# Nixie_Power_Suppy_v2_0_1.net
KiCad netlist of a schematic drawn in EAGLE
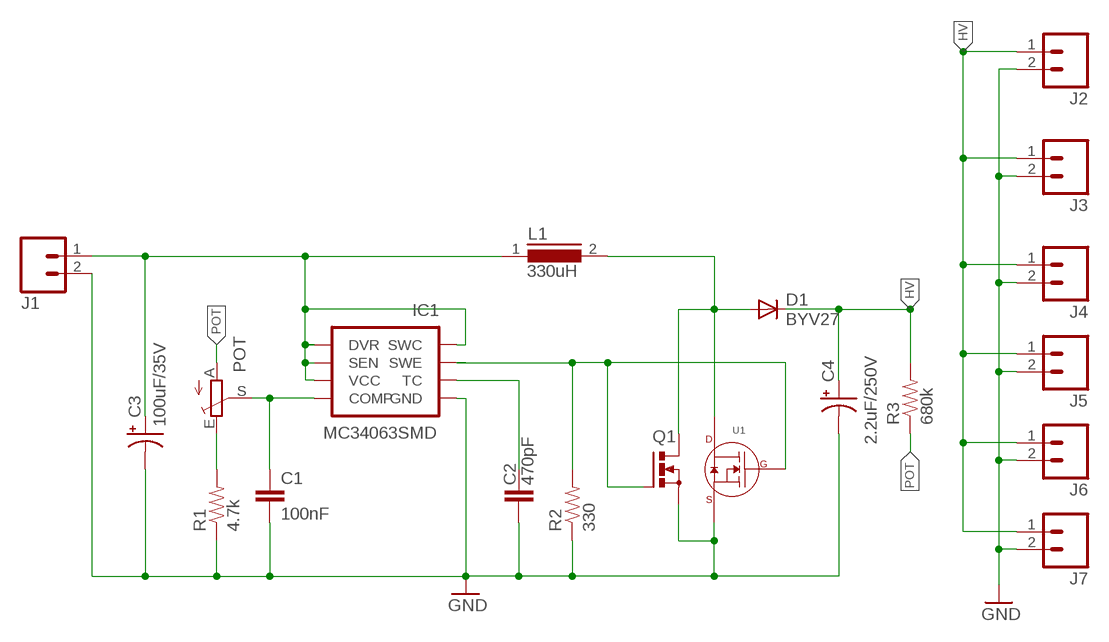
[diagram p0: schematic, sheet 1]

(export (version "E")
  (design (tool "Eeschema 10.0.6"))
  (components
    (comp (ref "C1")
      (value "100nF")
      (footprint "eagle-import:0805")
      (libsource (lib "eagle-import") (part "CAP0805"))
    )
    (comp (ref "C2")
      (value "470pF")
      (footprint "eagle-import:0805")
      (libsource (lib "eagle-import") (part "CAP0805"))
    )
    (comp (ref "C3")
      (value "100uF/35V")
      (footprint "eagle-import:CPOL-RADIAL-100UF-25V")
      (libsource (lib "eagle-import") (part "CAP_POLPTH1"))
    )
    (comp (ref "C4")
      (value "2.2uF/250V")
      (footprint "eagle-import:CPOL-RADIAL-100UF-25V")
      (libsource (lib "eagle-import") (part "CAP_POLPTH1"))
    )
    (comp (ref "D1")
      (value "BYV27")
      (footprint "eagle-import:SOD57-10")
      (libsource (lib "eagle-import") (part "BYV27"))
    )
    (comp (ref "IC1")
      (value "MC34063SMD")
      (footprint "eagle-import:SO08")
      (libsource (lib "eagle-import") (part "MC34063SMD"))
    )
    (comp (ref "J1")
      (value "M02LOCK")
      (footprint "eagle-import:1X02_LOCK")
      (libsource (lib "eagle-import") (part "M02LOCK"))
    )
    (comp (ref "J2")
      (value "M02LOCK")
      (footprint "eagle-import:1X02_LOCK")
      (libsource (lib "eagle-import") (part "M02LOCK"))
    )
    (comp (ref "J3")
      (value "M02LOCK")
      (footprint "eagle-import:1X02_LOCK")
      (libsource (lib "eagle-import") (part "M02LOCK"))
    )
    (comp (ref "J4")
      (value "M02LOCK")
      (footprint "eagle-import:1X02_LOCK")
      (libsource (lib "eagle-import") (part "M02LOCK"))
    )
    (comp (ref "J5")
      (value "M02LOCK")
      (footprint "eagle-import:1X02_LOCK")
      (libsource (lib "eagle-import") (part "M02LOCK"))
    )
    (comp (ref "J6")
      (value "M02LOCK")
      (footprint "eagle-import:1X02_LOCK")
      (libsource (lib "eagle-import") (part "M02LOCK"))
    )
    (comp (ref "J7")
      (value "M02LOCK")
      (footprint "eagle-import:1X02_LOCK")
      (libsource (lib "eagle-import") (part "M02LOCK"))
    )
    (comp (ref "L1")
      (value "330uH")
      (footprint "eagle-import:DR74")
      (libsource (lib "eagle-import") (part "DR74"))
    )
    (comp (ref "POT")
      (value "TRIM_EU-CA6V")
      (footprint "eagle-import:CA6V")
      (libsource (lib "eagle-import") (part "TRIM_EU-CA6V"))
    )
    (comp (ref "Q1")
      (value "PMOSFET_NTO220BV")
      (footprint "eagle-import:TO220BV")
      (libsource (lib "eagle-import") (part "PMOSFET_NTO220BV"))
    )
    (comp (ref "R1")
      (value "4.7k")
      (footprint "eagle-import:0805")
      (libsource (lib "eagle-import") (part "RESISTOR0805-RES"))
    )
    (comp (ref "R2")
      (value "330")
      (footprint "eagle-import:0805")
      (libsource (lib "eagle-import") (part "RESISTOR0805-RES"))
    )
    (comp (ref "R3")
      (value "680k")
      (footprint "eagle-import:0805")
      (libsource (lib "eagle-import") (part "RESISTOR0805-RES"))
    )
    (comp (ref "U1")
      (value "MOSFET_N-CHANNEL_SINGLE_TO-252-3")
      (footprint "eagle-import:TO-252-3")
      (libsource (lib "eagle-import") (part "MOSFET_N-CHANNEL_SINGLE_TO-252-3"))
    )
  )
  (nets
    (net (code "1") (name "GND") (class "Default")
      (node (ref "C1") (pin "2") (pinfunction "2_2") (pintype "passive"))
      (node (ref "C2") (pin "2") (pinfunction "2_2") (pintype "passive"))
      (node (ref "C3") (pin "2") (pinfunction "-_2") (pintype "passive"))
      (node (ref "C4") (pin "2") (pinfunction "-_2") (pintype "passive"))
      (node (ref "IC1") (pin "4") (pinfunction "GND_4") (pintype "bidirectional"))
      (node (ref "J1") (pin "2") (pinfunction "2_2") (pintype "passive"))
      (node (ref "J2") (pin "2") (pinfunction "2_2") (pintype "passive"))
      (node (ref "J3") (pin "2") (pinfunction "2_2") (pintype "passive"))
      (node (ref "J4") (pin "2") (pinfunction "2_2") (pintype "passive"))
      (node (ref "J5") (pin "2") (pinfunction "2_2") (pintype "passive"))
      (node (ref "J6") (pin "2") (pinfunction "2_2") (pintype "passive"))
      (node (ref "J7") (pin "2") (pinfunction "2_2") (pintype "passive"))
      (node (ref "Q1") (pin "S") (pinfunction "S_S") (pintype "passive"))
      (node (ref "R1") (pin "1") (pinfunction "1_1") (pintype "passive"))
      (node (ref "R2") (pin "1") (pinfunction "1_1") (pintype "passive"))
      (node (ref "U1") (pin "3") (pinfunction "SOURCE_3") (pintype "bidirectional"))
    )
    (net (code "2") (name "HV") (class "Default")
      (node (ref "C4") (pin "1") (pinfunction "+_1") (pintype "passive"))
      (node (ref "D1") (pin "C") (pinfunction "C_C") (pintype "passive"))
      (node (ref "J2") (pin "1") (pinfunction "1_1") (pintype "passive"))
      (node (ref "J3") (pin "1") (pinfunction "1_1") (pintype "passive"))
      (node (ref "J4") (pin "1") (pinfunction "1_1") (pintype "passive"))
      (node (ref "J5") (pin "1") (pinfunction "1_1") (pintype "passive"))
      (node (ref "J6") (pin "1") (pinfunction "1_1") (pintype "passive"))
      (node (ref "J7") (pin "1") (pinfunction "1_1") (pintype "passive"))
      (node (ref "R3") (pin "2") (pinfunction "2_2") (pintype "passive"))
    )
    (net (code "3") (name "Net-(C3-+)") (class "Default")
      (node (ref "C3") (pin "1") (pinfunction "+_1") (pintype "passive"))
      (node (ref "IC1") (pin "1") (pinfunction "SWC_1") (pintype "bidirectional"))
      (node (ref "IC1") (pin "6") (pinfunction "VCC_6") (pintype "bidirectional"))
      (node (ref "IC1") (pin "7") (pinfunction "SEN_7") (pintype "bidirectional"))
      (node (ref "IC1") (pin "8") (pinfunction "DVR_8") (pintype "bidirectional"))
      (node (ref "J1") (pin "1") (pinfunction "1_1") (pintype "passive"))
      (node (ref "L1") (pin "1") (pinfunction "1_1") (pintype "passive"))
    )
    (net (code "4") (name "Net-(IC1-COMP)") (class "Default")
      (node (ref "C1") (pin "1") (pinfunction "1_1") (pintype "passive"))
      (node (ref "IC1") (pin "5") (pinfunction "COMP_5") (pintype "bidirectional"))
      (node (ref "POT") (pin "S") (pinfunction "S_S") (pintype "passive"))
    )
    (net (code "5") (name "Net-(IC1-SWE)") (class "Default")
      (node (ref "IC1") (pin "2") (pinfunction "SWE_2") (pintype "bidirectional"))
      (node (ref "Q1") (pin "G") (pinfunction "G_G") (pintype "passive"))
      (node (ref "R2") (pin "2") (pinfunction "2_2") (pintype "passive"))
      (node (ref "U1") (pin "1") (pinfunction "GATE_1") (pintype "bidirectional"))
    )
    (net (code "6") (name "Net-(IC1-TC)") (class "Default")
      (node (ref "C2") (pin "1") (pinfunction "1_1") (pintype "passive"))
      (node (ref "IC1") (pin "3") (pinfunction "TC_3") (pintype "bidirectional"))
    )
    (net (code "7") (name "Net-(POT-PadE)") (class "Default")
      (node (ref "POT") (pin "E") (pinfunction "E_E") (pintype "passive"))
      (node (ref "R1") (pin "2") (pinfunction "2_2") (pintype "passive"))
    )
    (net (code "8") (name "Net-(U1-DRAIN)") (class "Default")
      (node (ref "D1") (pin "A") (pinfunction "A_A") (pintype "passive"))
      (node (ref "L1") (pin "2") (pinfunction "2_2") (pintype "passive"))
      (node (ref "Q1") (pin "D") (pinfunction "D_D") (pintype "passive"))
      (node (ref "U1") (pin "PAD") (pinfunction "DRAIN_PAD") (pintype "bidirectional"))
    )
    (net (code "9") (name "POT") (class "Default")
      (node (ref "POT") (pin "A") (pinfunction "A_A") (pintype "passive"))
      (node (ref "R3") (pin "1") (pinfunction "1_1") (pintype "passive"))
    )
  )
)
